# Chocolate_Vending_Machine_V3_2.net
KiCad netlist of a schematic drawn in Altium Designer
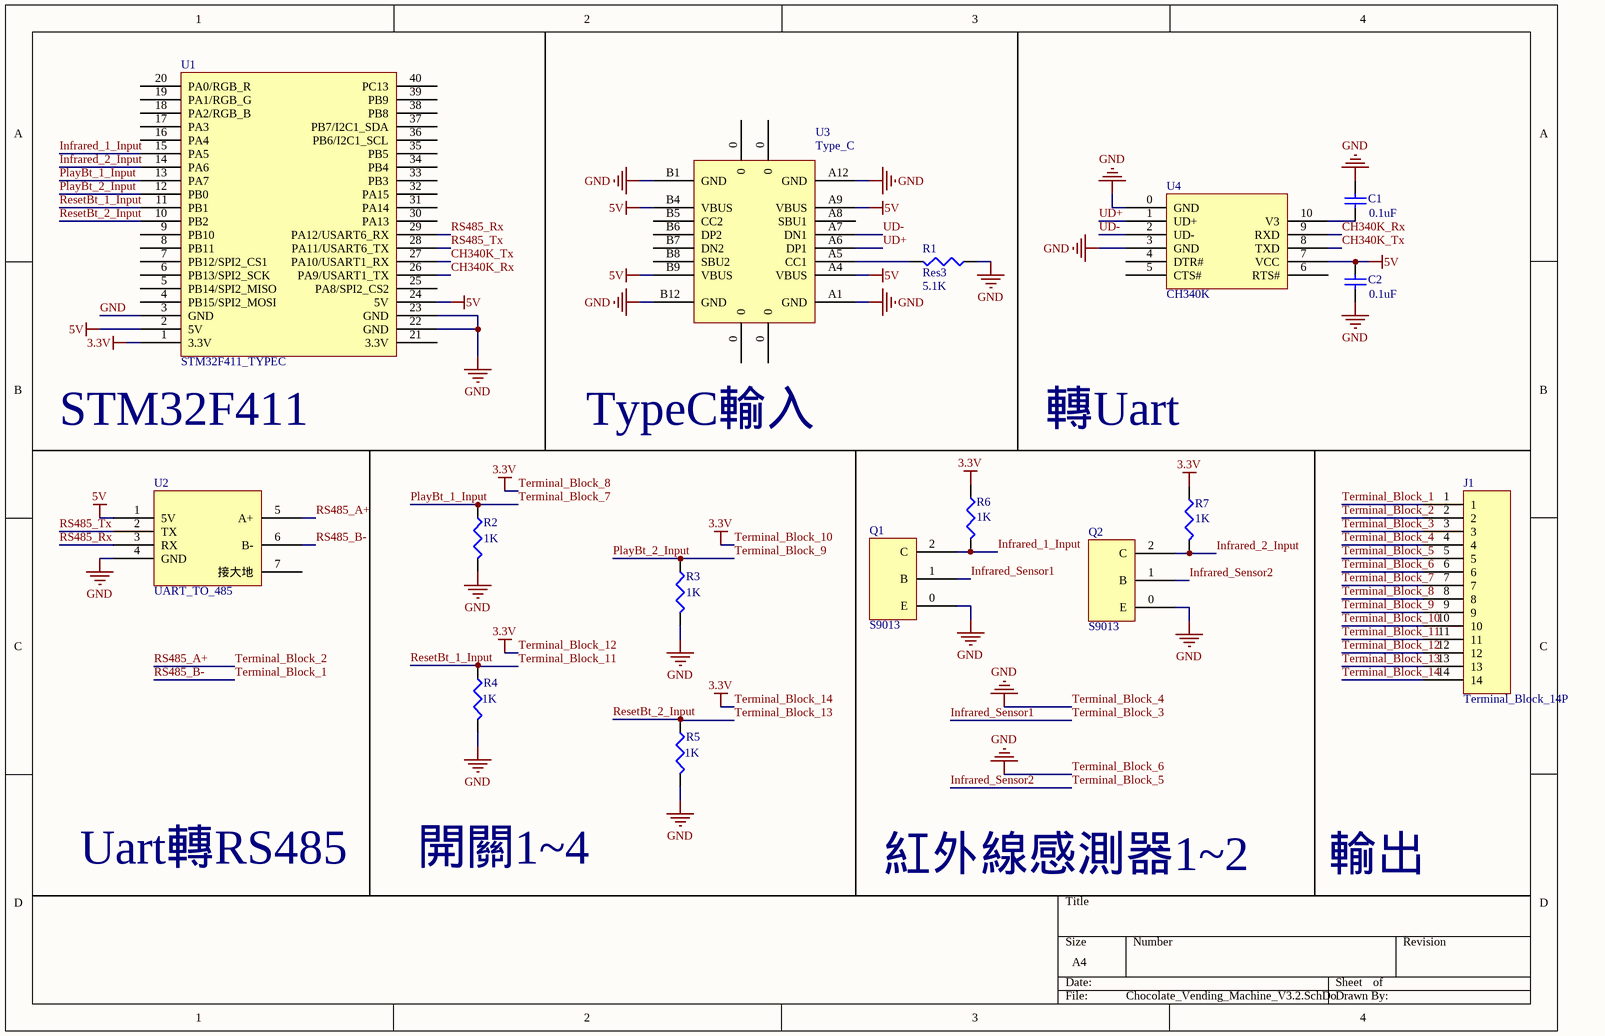
[diagram p0: Chocolate_Vending_Machine_V3.2.SchDoc]

(export (version "E")
  (design (tool "Eeschema 10.0.6"))
  (components
    (comp (ref "C1")
      (value "0.1uF")
      (footprint "1608[0603]")
      (description "Capacitor (Semiconductor SIM Model)")
      (fields (field (name "Comment") "Cap Semi") (field (name "PUBLISHER") "Altium Limited"))
      (libsource (lib "Miscellaneous Devices") (part "Cap Semi"))
    )
    (comp (ref "C2")
      (value "0.1uF")
      (footprint "1608[0603]")
      (description "Capacitor (Semiconductor SIM Model)")
      (fields (field (name "Comment") "Cap Semi") (field (name "PUBLISHER") "Altium Limited"))
      (libsource (lib "Miscellaneous Devices") (part "Cap Semi"))
    )
    (comp (ref "J1")
      (value "Terminal_Block_14P")
      (footprint "terminal_block_14P")
      (libsource (lib "Lab_share") (part "Terminal_Block_14P"))
    )
    (comp (ref "Q1") (value "S9013") (footprint "S9013") (libsource (lib "Lab_share") (part "S9013")))
    (comp (ref "Q2") (value "S9013") (footprint "S9013") (libsource (lib "Lab_share") (part "S9013")))
    (comp (ref "R1")
      (value "Res3")
      (footprint "J1-0603")
      (description "Resistor")
      (fields (field (name "ALTIUM_VALUE") "5.1K") (field (name "PUBLISHER") "Altium Limited"))
      (libsource (lib "Miscellaneous Devices") (part "Res3"))
    )
    (comp (ref "R2")
      (value "1K")
      (footprint "J1-0603")
      (description "Resistor")
      (fields (field (name "Comment") "Res3") (field (name "PUBLISHER") "Altium Limited"))
      (libsource (lib "Miscellaneous Devices") (part "Res3"))
    )
    (comp (ref "R3")
      (value "1K")
      (footprint "J1-0603")
      (description "Resistor")
      (fields (field (name "Comment") "Res3") (field (name "PUBLISHER") "Altium Limited"))
      (libsource (lib "Miscellaneous Devices") (part "Res3"))
    )
    (comp (ref "R4")
      (value "1K")
      (footprint "J1-0603")
      (description "Resistor")
      (fields (field (name "Comment") "Res3") (field (name "PUBLISHER") "Altium Limited"))
      (libsource (lib "Miscellaneous Devices") (part "Res3"))
    )
    (comp (ref "R5")
      (value "1K")
      (footprint "J1-0603")
      (description "Resistor")
      (fields (field (name "Comment") "Res3") (field (name "PUBLISHER") "Altium Limited"))
      (libsource (lib "Miscellaneous Devices") (part "Res3"))
    )
    (comp (ref "R6")
      (value "1K")
      (footprint "J1-0603")
      (description "Resistor")
      (fields (field (name "Comment") "Res3") (field (name "PUBLISHER") "Altium Limited"))
      (libsource (lib "Miscellaneous Devices") (part "Res3"))
    )
    (comp (ref "R7")
      (value "1K")
      (footprint "J1-0603")
      (description "Resistor")
      (fields (field (name "Comment") "Res3") (field (name "PUBLISHER") "Altium Limited"))
      (libsource (lib "Miscellaneous Devices") (part "Res3"))
    )
    (comp (ref "U1")
      (value "STM32F411_TYPEC")
      (footprint "STM32F411_TypeC")
      (libsource (lib "Lab_share") (part "STM32F411_TYPEC"))
    )
    (comp (ref "U2")
      (value "UART_TO_485")
      (footprint "UART_TO_RS485")
      (libsource (lib "Lab_share") (part "UART_TO_485"))
    )
    (comp (ref "U3") (value "Type_C") (footprint "Type_C_V2") (libsource (lib "Lab_share") (part "Type_C")))
    (comp (ref "U4") (value "CH340K") (footprint "CH340K_V1") (libsource (lib "Lab_share") (part "CH340K")))
  )
  (nets
    (net (code "1") (name "/CH340K_Rx") (class "Default")
      (node (ref "U1") (pin "26") (pinfunction "PA9/USART1_TX_26") (pintype "passive"))
      (node (ref "U4") (pin "9") (pinfunction "RXD_9") (pintype "passive"))
    )
    (net (code "2") (name "/CH340K_Tx") (class "Default")
      (node (ref "U1") (pin "27") (pinfunction "PA10/USART1_RX_27") (pintype "passive"))
      (node (ref "U4") (pin "8") (pinfunction "TXD_8") (pintype "passive"))
    )
    (net (code "3") (name "/Infrared_1_Input") (class "Default")
      (node (ref "Q1") (pin "2") (pinfunction "C_2") (pintype "passive"))
      (node (ref "R6") (pin "2") (pinfunction "2_2") (pintype "passive"))
      (node (ref "U1") (pin "15") (pinfunction "PA5_15") (pintype "passive"))
    )
    (net (code "4") (name "/Infrared_2_Input") (class "Default")
      (node (ref "Q2") (pin "2") (pinfunction "C_2") (pintype "passive"))
      (node (ref "R7") (pin "2") (pinfunction "2_2") (pintype "passive"))
      (node (ref "U1") (pin "14") (pinfunction "PA6_14") (pintype "passive"))
    )
    (net (code "5") (name "/Infrared_Sensor1") (class "Default")
      (node (ref "J1") (pin "3") (pinfunction "3_3") (pintype "passive"))
      (node (ref "Q1") (pin "1") (pinfunction "B_1") (pintype "passive"))
    )
    (net (code "6") (name "/Infrared_Sensor2") (class "Default")
      (node (ref "J1") (pin "5") (pinfunction "5_5") (pintype "passive"))
      (node (ref "Q2") (pin "1") (pinfunction "B_1") (pintype "passive"))
    )
    (net (code "7") (name "/PlayBt_1_Input") (class "Default")
      (node (ref "J1") (pin "7") (pinfunction "7_7") (pintype "passive"))
      (node (ref "R2") (pin "1") (pinfunction "1_1") (pintype "passive"))
      (node (ref "U1") (pin "13") (pinfunction "PA7_13") (pintype "passive"))
    )
    (net (code "8") (name "/PlayBt_2_Input") (class "Default")
      (node (ref "J1") (pin "9") (pinfunction "9_9") (pintype "passive"))
      (node (ref "R3") (pin "1") (pinfunction "1_1") (pintype "passive"))
      (node (ref "U1") (pin "12") (pinfunction "PB0_12") (pintype "passive"))
    )
    (net (code "9") (name "/RS485_A+") (class "Default")
      (node (ref "J1") (pin "2") (pinfunction "2_2") (pintype "passive"))
      (node (ref "U2") (pin "5") (pinfunction "A+_5") (pintype "passive"))
    )
    (net (code "10") (name "/RS485_B-") (class "Default")
      (node (ref "J1") (pin "1") (pinfunction "1_1") (pintype "passive"))
      (node (ref "U2") (pin "6") (pinfunction "B-_6") (pintype "passive"))
    )
    (net (code "11") (name "/RS485_Rx") (class "Default")
      (node (ref "U1") (pin "29") (pinfunction "PA12/USART6_RX_29") (pintype "passive"))
      (node (ref "U2") (pin "3") (pinfunction "RX_3") (pintype "passive"))
    )
    (net (code "12") (name "/RS485_Tx") (class "Default")
      (node (ref "U1") (pin "28") (pinfunction "PA11/USART6_TX_28") (pintype "passive"))
      (node (ref "U2") (pin "2") (pinfunction "TX_2") (pintype "passive"))
    )
    (net (code "13") (name "/ResetBt_1_Input") (class "Default")
      (node (ref "J1") (pin "11") (pinfunction "11_11") (pintype "passive"))
      (node (ref "R4") (pin "1") (pinfunction "1_1") (pintype "passive"))
      (node (ref "U1") (pin "11") (pinfunction "PB1_11") (pintype "passive"))
    )
    (net (code "14") (name "/ResetBt_2_Input") (class "Default")
      (node (ref "J1") (pin "13") (pinfunction "13_13") (pintype "passive"))
      (node (ref "R5") (pin "1") (pinfunction "1_1") (pintype "passive"))
      (node (ref "U1") (pin "10") (pinfunction "PB2_10") (pintype "passive"))
    )
    (net (code "15") (name "/UD+") (class "Default")
      (node (ref "U3") (pin "A6") (pinfunction "DP1_A6") (pintype "passive"))
      (node (ref "U4") (pin "1") (pinfunction "UD+_1") (pintype "passive"))
    )
    (net (code "16") (name "/UD-") (class "Default")
      (node (ref "U3") (pin "A7") (pinfunction "DN1_A7") (pintype "passive"))
      (node (ref "U4") (pin "2") (pinfunction "UD-_2") (pintype "passive"))
    )
    (net (code "17") (name "3.3V") (class "Default")
      (node (ref "J1") (pin "10") (pinfunction "10_10") (pintype "passive"))
      (node (ref "J1") (pin "12") (pinfunction "12_12") (pintype "passive"))
      (node (ref "J1") (pin "14") (pinfunction "14_14") (pintype "passive"))
      (node (ref "J1") (pin "8") (pinfunction "8_8") (pintype "passive"))
      (node (ref "R6") (pin "1") (pinfunction "1_1") (pintype "passive"))
      (node (ref "R7") (pin "1") (pinfunction "1_1") (pintype "passive"))
      (node (ref "U1") (pin "1") (pinfunction "3.3V_1") (pintype "passive"))
    )
    (net (code "18") (name "5V") (class "Default")
      (node (ref "C2") (pin "2") (pinfunction "2_2") (pintype "passive"))
      (node (ref "U1") (pin "2") (pinfunction "5V_2") (pintype "passive"))
      (node (ref "U1") (pin "24") (pinfunction "5V_24") (pintype "passive"))
      (node (ref "U2") (pin "1") (pinfunction "5V_1") (pintype "passive"))
      (node (ref "U3") (pin "A4") (pinfunction "VBUS_A4") (pintype "passive"))
      (node (ref "U3") (pin "A9") (pinfunction "VBUS_A9") (pintype "passive"))
      (node (ref "U3") (pin "B4") (pinfunction "VBUS_B4") (pintype "passive"))
      (node (ref "U3") (pin "B9") (pinfunction "VBUS_B9") (pintype "passive"))
      (node (ref "U4") (pin "7") (pinfunction "VCC_7") (pintype "passive"))
    )
    (net (code "19") (name "GND") (class "Default")
      (node (ref "C1") (pin "2") (pinfunction "2_2") (pintype "passive"))
      (node (ref "C2") (pin "1") (pinfunction "1_1") (pintype "passive"))
      (node (ref "J1") (pin "4") (pinfunction "4_4") (pintype "passive"))
      (node (ref "J1") (pin "6") (pinfunction "6_6") (pintype "passive"))
      (node (ref "Q1") (pin "0") (pinfunction "E_0") (pintype "passive"))
      (node (ref "Q2") (pin "0") (pinfunction "E_0") (pintype "passive"))
      (node (ref "R1") (pin "1") (pinfunction "1_1") (pintype "passive"))
      (node (ref "R2") (pin "2") (pinfunction "2_2") (pintype "passive"))
      (node (ref "R3") (pin "2") (pinfunction "2_2") (pintype "passive"))
      (node (ref "R4") (pin "2") (pinfunction "2_2") (pintype "passive"))
      (node (ref "R5") (pin "2") (pinfunction "2_2") (pintype "passive"))
      (node (ref "U1") (pin "22") (pinfunction "GND_22") (pintype "passive"))
      (node (ref "U1") (pin "23") (pinfunction "GND_23") (pintype "passive"))
      (node (ref "U1") (pin "3") (pinfunction "GND_3") (pintype "passive"))
      (node (ref "U2") (pin "4") (pinfunction "GND_4") (pintype "passive"))
      (node (ref "U3") (pin "A1") (pinfunction "GND_A1") (pintype "passive"))
      (node (ref "U3") (pin "A12") (pinfunction "GND_A12") (pintype "passive"))
      (node (ref "U3") (pin "B1") (pinfunction "GND_B1") (pintype "passive"))
      (node (ref "U3") (pin "B12") (pinfunction "GND_B12") (pintype "passive"))
      (node (ref "U4") (pin "0") (pinfunction "GND_0") (pintype "passive"))
      (node (ref "U4") (pin "3") (pinfunction "GND_3") (pintype "passive"))
    )
    (net (code "20") (name "Net-(U3-CC1)") (class "Default")
      (node (ref "R1") (pin "2") (pinfunction "2_2") (pintype "passive"))
      (node (ref "U3") (pin "A5") (pinfunction "CC1_A5") (pintype "passive"))
    )
    (net (code "21") (name "Net-(U4-V3)") (class "Default")
      (node (ref "C1") (pin "1") (pinfunction "1_1") (pintype "passive"))
      (node (ref "U4") (pin "10") (pinfunction "V3_10") (pintype "passive"))
    )
    (net (code "22") (name "unconnected-(U1-3.3V-Pad21)") (class "Default")
      (node (ref "U1") (pin "21") (pinfunction "3.3V_21") (pintype "passive"))
    )
    (net (code "23") (name "unconnected-(U1-PA0{slash}RGB_R-Pad20)") (class "Default")
      (node (ref "U1") (pin "20") (pinfunction "PA0/RGB_R_20") (pintype "passive"))
    )
    (net (code "24") (name "unconnected-(U1-PA1{slash}RGB_G-Pad19)") (class "Default")
      (node (ref "U1") (pin "19") (pinfunction "PA1/RGB_G_19") (pintype "passive"))
    )
    (net (code "25") (name "unconnected-(U1-PA2{slash}RGB_B-Pad18)") (class "Default")
      (node (ref "U1") (pin "18") (pinfunction "PA2/RGB_B_18") (pintype "passive"))
    )
    (net (code "26") (name "unconnected-(U1-PA3-Pad17)") (class "Default")
      (node (ref "U1") (pin "17") (pinfunction "PA3_17") (pintype "passive"))
    )
    (net (code "27") (name "unconnected-(U1-PA4-Pad16)") (class "Default")
      (node (ref "U1") (pin "16") (pinfunction "PA4_16") (pintype "passive"))
    )
    (net (code "28") (name "unconnected-(U1-PA8{slash}SPI2_CS2-Pad25)") (class "Default")
      (node (ref "U1") (pin "25") (pinfunction "PA8/SPI2_CS2_25") (pintype "passive"))
    )
    (net (code "29") (name "unconnected-(U1-PA13-Pad30)") (class "Default")
      (node (ref "U1") (pin "30") (pinfunction "PA13_30") (pintype "passive"))
    )
    (net (code "30") (name "unconnected-(U1-PA14-Pad31)") (class "Default")
      (node (ref "U1") (pin "31") (pinfunction "PA14_31") (pintype "passive"))
    )
    (net (code "31") (name "unconnected-(U1-PA15-Pad32)") (class "Default")
      (node (ref "U1") (pin "32") (pinfunction "PA15_32") (pintype "passive"))
    )
    (net (code "32") (name "unconnected-(U1-PB3-Pad33)") (class "Default")
      (node (ref "U1") (pin "33") (pinfunction "PB3_33") (pintype "passive"))
    )
    (net (code "33") (name "unconnected-(U1-PB4-Pad34)") (class "Default")
      (node (ref "U1") (pin "34") (pinfunction "PB4_34") (pintype "passive"))
    )
    (net (code "34") (name "unconnected-(U1-PB5-Pad35)") (class "Default")
      (node (ref "U1") (pin "35") (pinfunction "PB5_35") (pintype "passive"))
    )
    (net (code "35") (name "unconnected-(U1-PB6{slash}I2C1_SCL-Pad36)") (class "Default")
      (node (ref "U1") (pin "36") (pinfunction "PB6/I2C1_SCL_36") (pintype "passive"))
    )
    (net (code "36") (name "unconnected-(U1-PB7{slash}I2C1_SDA-Pad37)") (class "Default")
      (node (ref "U1") (pin "37") (pinfunction "PB7/I2C1_SDA_37") (pintype "passive"))
    )
    (net (code "37") (name "unconnected-(U1-PB8-Pad38)") (class "Default")
      (node (ref "U1") (pin "38") (pinfunction "PB8_38") (pintype "passive"))
    )
    (net (code "38") (name "unconnected-(U1-PB9-Pad39)") (class "Default")
      (node (ref "U1") (pin "39") (pinfunction "PB9_39") (pintype "passive"))
    )
    (net (code "39") (name "unconnected-(U1-PB10-Pad9)") (class "Default")
      (node (ref "U1") (pin "9") (pinfunction "PB10_9") (pintype "passive"))
    )
    (net (code "40") (name "unconnected-(U1-PB11-Pad8)") (class "Default")
      (node (ref "U1") (pin "8") (pinfunction "PB11_8") (pintype "passive"))
    )
    (net (code "41") (name "unconnected-(U1-PB12{slash}SPI2_CS1-Pad7)") (class "Default")
      (node (ref "U1") (pin "7") (pinfunction "PB12/SPI2_CS1_7") (pintype "passive"))
    )
    (net (code "42") (name "unconnected-(U1-PB13{slash}SPI2_SCK-Pad6)") (class "Default")
      (node (ref "U1") (pin "6") (pinfunction "PB13/SPI2_SCK_6") (pintype "passive"))
    )
    (net (code "43") (name "unconnected-(U1-PB14{slash}SPI2_MISO-Pad5)") (class "Default")
      (node (ref "U1") (pin "5") (pinfunction "PB14/SPI2_MISO_5") (pintype "passive"))
    )
    (net (code "44") (name "unconnected-(U1-PB15{slash}SPI2_MOSI-Pad4)") (class "Default")
      (node (ref "U1") (pin "4") (pinfunction "PB15/SPI2_MOSI_4") (pintype "passive"))
    )
    (net (code "45") (name "unconnected-(U1-PC13-Pad40)") (class "Default")
      (node (ref "U1") (pin "40") (pinfunction "PC13_40") (pintype "passive"))
    )
    (net (code "46") (name "unconnected-(U2-接大地-Pad7)") (class "Default")
      (node (ref "U2") (pin "7") (pinfunction "接大地_7") (pintype "passive"))
    )
    (net (code "47") (name "unconnected-(U3-CC2-PadB5)") (class "Default")
      (node (ref "U3") (pin "B5") (pinfunction "CC2_B5") (pintype "passive"))
    )
    (net (code "48") (name "unconnected-(U3-DN2-PadB7)") (class "Default")
      (node (ref "U3") (pin "B7") (pinfunction "DN2_B7") (pintype "passive"))
    )
    (net (code "49") (name "unconnected-(U3-DP2-PadB6)") (class "Default")
      (node (ref "U3") (pin "B6") (pinfunction "DP2_B6") (pintype "passive"))
    )
    (net (code "50") (name "unconnected-(U3-Pad0)") (class "Default")
      (node (ref "U3") (pin "0") (pinfunction "0_0") (pintype "passive"))
    )
    (net (code "51") (name "unconnected-(U3-Pad0)_1") (class "Default")
      (node (ref "U3") (pin "0") (pinfunction "0_0") (pintype "passive"))
    )
    (net (code "52") (name "unconnected-(U3-Pad0)_2") (class "Default")
      (node (ref "U3") (pin "0") (pinfunction "0_0") (pintype "passive"))
    )
    (net (code "53") (name "unconnected-(U3-Pad0)_3") (class "Default")
      (node (ref "U3") (pin "0") (pinfunction "0_0") (pintype "passive"))
    )
    (net (code "54") (name "unconnected-(U3-SBU1-PadA8)") (class "Default")
      (node (ref "U3") (pin "A8") (pinfunction "SBU1_A8") (pintype "passive"))
    )
    (net (code "55") (name "unconnected-(U3-SBU2-PadB8)") (class "Default")
      (node (ref "U3") (pin "B8") (pinfunction "SBU2_B8") (pintype "passive"))
    )
    (net (code "56") (name "unconnected-(U4-CTS#-Pad5)") (class "Default")
      (node (ref "U4") (pin "5") (pinfunction "CTS#_5") (pintype "passive"))
    )
    (net (code "57") (name "unconnected-(U4-DTR#-Pad4)") (class "Default")
      (node (ref "U4") (pin "4") (pinfunction "DTR#_4") (pintype "passive"))
    )
    (net (code "58") (name "unconnected-(U4-RTS#-Pad6)") (class "Default")
      (node (ref "U4") (pin "6") (pinfunction "RTS#_6") (pintype "passive"))
    )
  )
)
